# gt-jtx.net
KiCad netlist of a schematic drawn in EAGLE
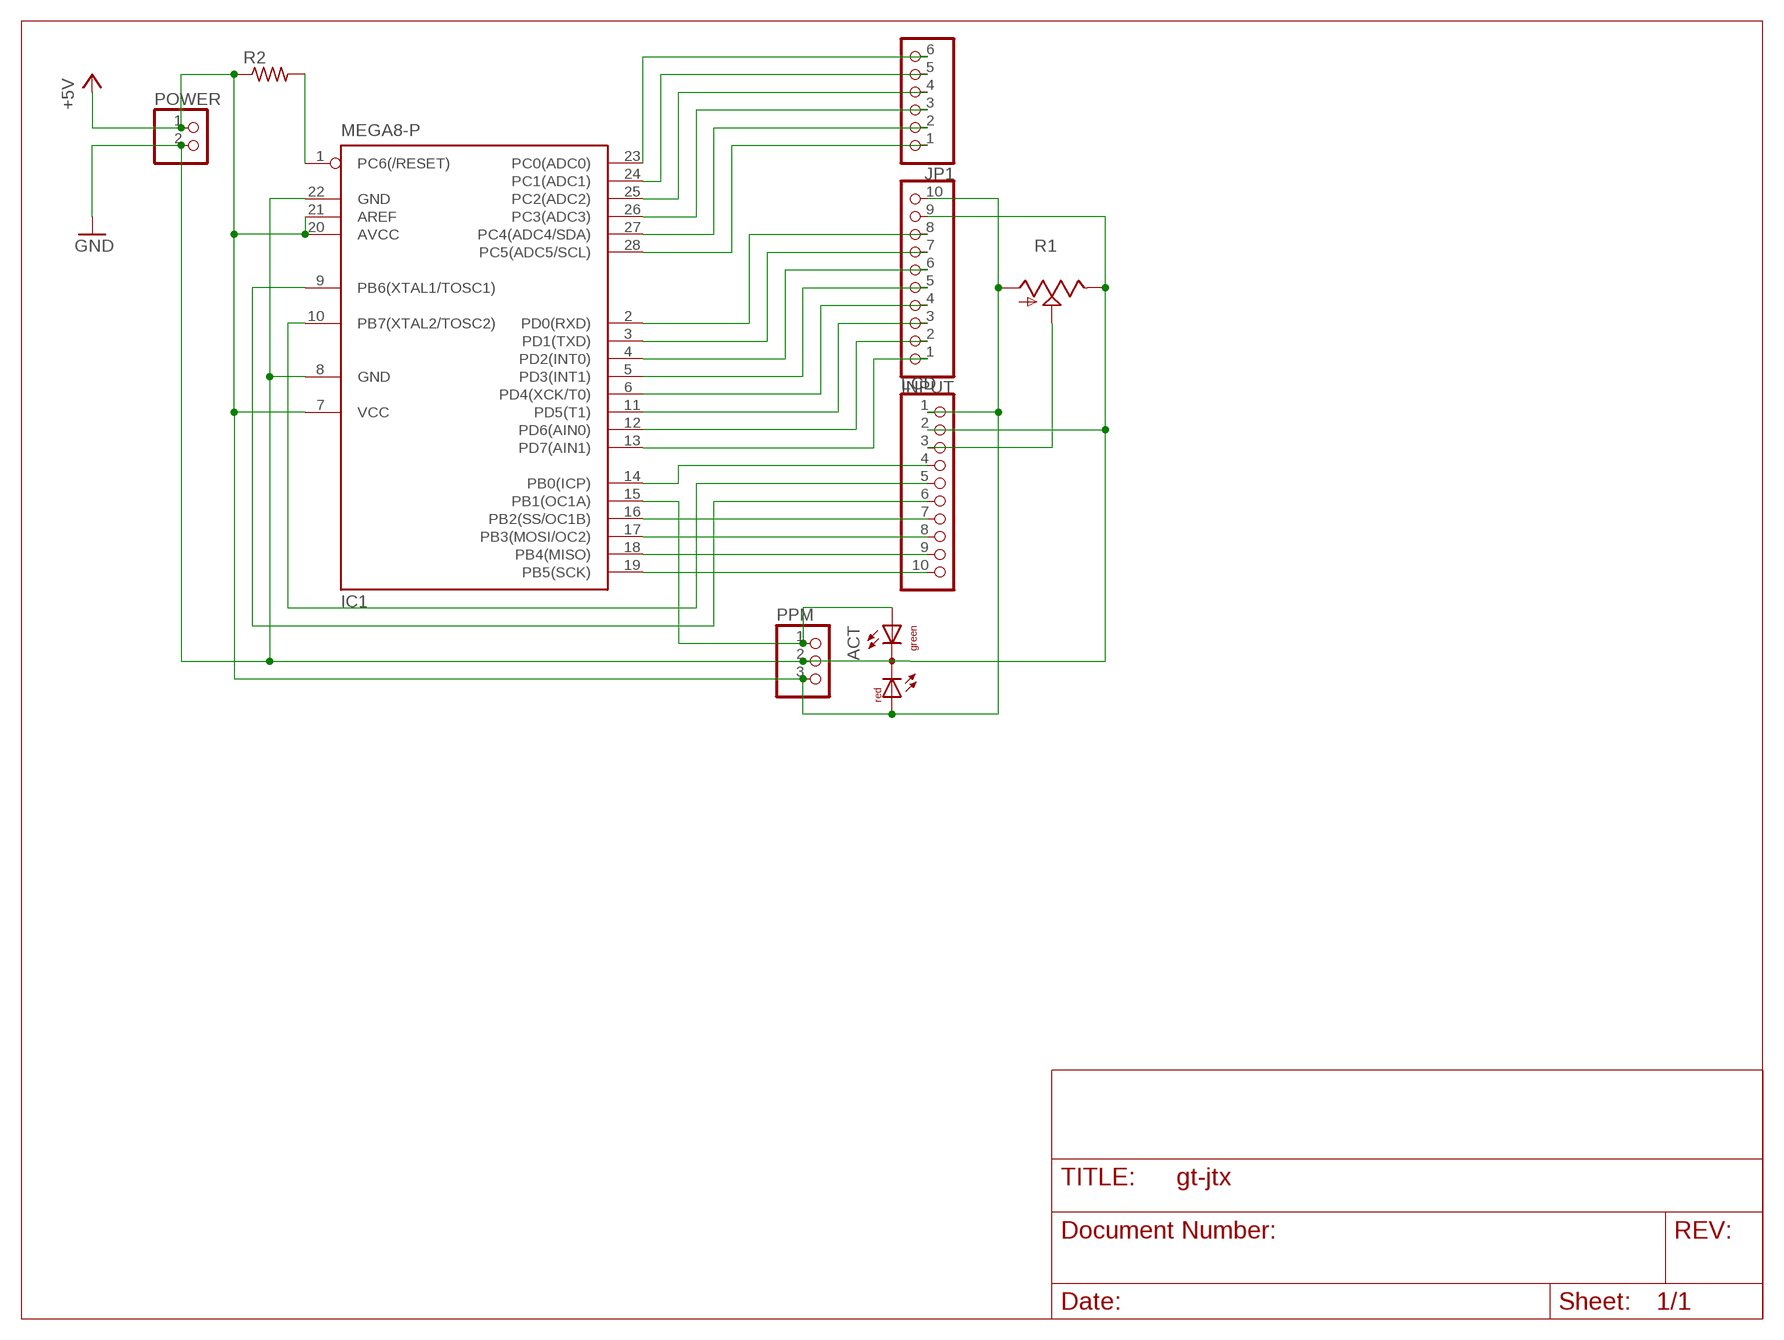
[diagram p0: schematic, sheet 1]

(export (version "E")
  (design (tool "Eeschema 10.0.6"))
  (components
    (comp (ref "ACT")
      (value "DUOLED-RG-C")
      (footprint "eagle-import:DUOLED-C-5MM")
      (libsource (lib "eagle-import") (part "DUOLED-RG-C"))
    )
    (comp (ref "IC1")
      (value "MEGA8-P")
      (footprint "eagle-import:DIL28-3")
      (libsource (lib "eagle-import") (part "MEGA8-P"))
    )
    (comp (ref "INPUT")
      (value "PINHD-1X10")
      (footprint "eagle-import:1X10")
      (libsource (lib "eagle-import") (part "PINHD-1X10"))
    )
    (comp (ref "JP1")
      (value "PINHD-1X6")
      (footprint "eagle-import:1X06")
      (libsource (lib "eagle-import") (part "PINHD-1X6"))
    )
    (comp (ref "LCD")
      (value "PINHD-1X10")
      (footprint "eagle-import:1X10")
      (libsource (lib "eagle-import") (part "PINHD-1X10"))
    )
    (comp (ref "POWER")
      (value "PINHD-1X2")
      (footprint "eagle-import:1X02")
      (libsource (lib "eagle-import") (part "PINHD-1X2"))
    )
    (comp (ref "PPM")
      (value "PINHD-1X3")
      (footprint "eagle-import:1X03")
      (libsource (lib "eagle-import") (part "PINHD-1X3"))
    )
    (comp (ref "R1")
      (value "TRIM_US-CA6V")
      (footprint "eagle-import:CA6V")
      (libsource (lib "eagle-import") (part "TRIM_US-CA6V"))
    )
    (comp (ref "R2")
      (value "R-US_0204/2V")
      (footprint "eagle-import:0204V")
      (libsource (lib "eagle-import") (part "R-US_0204/2V"))
    )
  )
  (nets
    (net (code "1") (name "+5V") (class "Default")
      (node (ref "ACT") (pin "AR") (pinfunction "AR_AR") (pintype "passive"))
      (node (ref "IC1") (pin "20") (pinfunction "AVCC_20") (pintype "power_in"))
      (node (ref "IC1") (pin "21") (pinfunction "AREF_21") (pintype "passive"))
      (node (ref "IC1") (pin "7") (pinfunction "VCC_7") (pintype "power_in"))
      (node (ref "INPUT") (pin "10") (pinfunction "10_10") (pintype "passive"))
      (node (ref "LCD") (pin "1") (pinfunction "1_1") (pintype "passive"))
      (node (ref "POWER") (pin "1") (pinfunction "1_1") (pintype "passive"))
      (node (ref "PPM") (pin "3") (pinfunction "3_3") (pintype "passive"))
      (node (ref "R1") (pin "A") (pinfunction "A_A") (pintype "passive"))
      (node (ref "R2") (pin "1") (pinfunction "1_1") (pintype "passive"))
    )
    (net (code "2") (name "GND") (class "Default")
      (node (ref "ACT") (pin "C") (pinfunction "C_C") (pintype "passive"))
      (node (ref "IC1") (pin "22") (pinfunction "GND_22") (pintype "power_in"))
      (node (ref "IC1") (pin "8") (pinfunction "GND_8") (pintype "power_in"))
      (node (ref "INPUT") (pin "9") (pinfunction "9_9") (pintype "passive"))
      (node (ref "LCD") (pin "2") (pinfunction "2_2") (pintype "passive"))
      (node (ref "POWER") (pin "2") (pinfunction "2_2") (pintype "passive"))
      (node (ref "PPM") (pin "2") (pinfunction "2_2") (pintype "passive"))
      (node (ref "R1") (pin "E") (pinfunction "E_E") (pintype "passive"))
    )
    (net (code "3") (name "Net-(ACT-AG)") (class "Default")
      (node (ref "ACT") (pin "AX") (pinfunction "AG_AX") (pintype "passive"))
      (node (ref "IC1") (pin "15") (pinfunction "PB1(OC1A)_15") (pintype "bidirectional"))
      (node (ref "PPM") (pin "1") (pinfunction "1_1") (pintype "passive"))
    )
    (net (code "4") (name "Net-(IC1-PB0(ICP))") (class "Default")
      (node (ref "IC1") (pin "14") (pinfunction "PB0(ICP)_14") (pintype "bidirectional"))
      (node (ref "LCD") (pin "4") (pinfunction "4_4") (pintype "passive"))
    )
    (net (code "5") (name "Net-(IC1-PB2(SS{slash}OC1B))") (class "Default")
      (node (ref "IC1") (pin "16") (pinfunction "PB2(SS/OC1B)_16") (pintype "bidirectional"))
      (node (ref "LCD") (pin "7") (pinfunction "7_7") (pintype "passive"))
    )
    (net (code "6") (name "Net-(IC1-PB3(MOSI{slash}OC2))") (class "Default")
      (node (ref "IC1") (pin "17") (pinfunction "PB3(MOSI/OC2)_17") (pintype "bidirectional"))
      (node (ref "LCD") (pin "8") (pinfunction "8_8") (pintype "passive"))
    )
    (net (code "7") (name "Net-(IC1-PB4(MISO))") (class "Default")
      (node (ref "IC1") (pin "18") (pinfunction "PB4(MISO)_18") (pintype "bidirectional"))
      (node (ref "LCD") (pin "9") (pinfunction "9_9") (pintype "passive"))
    )
    (net (code "8") (name "Net-(IC1-PB5(SCK))") (class "Default")
      (node (ref "IC1") (pin "19") (pinfunction "PB5(SCK)_19") (pintype "bidirectional"))
      (node (ref "LCD") (pin "10") (pinfunction "10_10") (pintype "passive"))
    )
    (net (code "9") (name "Net-(IC1-PB6(XTAL1{slash}TOSC1))") (class "Default")
      (node (ref "IC1") (pin "9") (pinfunction "PB6(XTAL1/TOSC1)_9") (pintype "bidirectional"))
      (node (ref "LCD") (pin "6") (pinfunction "6_6") (pintype "passive"))
    )
    (net (code "10") (name "Net-(IC1-PB7(XTAL2{slash}TOSC2))") (class "Default")
      (node (ref "IC1") (pin "10") (pinfunction "PB7(XTAL2/TOSC2)_10") (pintype "bidirectional"))
      (node (ref "LCD") (pin "5") (pinfunction "5_5") (pintype "passive"))
    )
    (net (code "11") (name "Net-(IC1-PC0(ADC0))") (class "Default")
      (node (ref "IC1") (pin "23") (pinfunction "PC0(ADC0)_23") (pintype "bidirectional"))
      (node (ref "JP1") (pin "6") (pinfunction "6_6") (pintype "passive"))
    )
    (net (code "12") (name "Net-(IC1-PC1(ADC1))") (class "Default")
      (node (ref "IC1") (pin "24") (pinfunction "PC1(ADC1)_24") (pintype "bidirectional"))
      (node (ref "JP1") (pin "5") (pinfunction "5_5") (pintype "passive"))
    )
    (net (code "13") (name "Net-(IC1-PC2(ADC2))") (class "Default")
      (node (ref "IC1") (pin "25") (pinfunction "PC2(ADC2)_25") (pintype "bidirectional"))
      (node (ref "JP1") (pin "4") (pinfunction "4_4") (pintype "passive"))
    )
    (net (code "14") (name "Net-(IC1-PC3(ADC3))") (class "Default")
      (node (ref "IC1") (pin "26") (pinfunction "PC3(ADC3)_26") (pintype "bidirectional"))
      (node (ref "JP1") (pin "3") (pinfunction "3_3") (pintype "passive"))
    )
    (net (code "15") (name "Net-(IC1-PC4(ADC4{slash}SDA))") (class "Default")
      (node (ref "IC1") (pin "27") (pinfunction "PC4(ADC4/SDA)_27") (pintype "bidirectional"))
      (node (ref "JP1") (pin "2") (pinfunction "2_2") (pintype "passive"))
    )
    (net (code "16") (name "Net-(IC1-PC5(ADC5{slash}SCL))") (class "Default")
      (node (ref "IC1") (pin "28") (pinfunction "PC5(ADC5/SCL)_28") (pintype "bidirectional"))
      (node (ref "JP1") (pin "1") (pinfunction "1_1") (pintype "passive"))
    )
    (net (code "17") (name "Net-(IC1-PC6({slash}RESET))") (class "Default")
      (node (ref "IC1") (pin "1") (pinfunction "PC6(/RESET)_1") (pintype "bidirectional"))
      (node (ref "R2") (pin "2") (pinfunction "2_2") (pintype "passive"))
    )
    (net (code "18") (name "Net-(IC1-PD0(RXD))") (class "Default")
      (node (ref "IC1") (pin "2") (pinfunction "PD0(RXD)_2") (pintype "bidirectional"))
      (node (ref "INPUT") (pin "8") (pinfunction "8_8") (pintype "passive"))
    )
    (net (code "19") (name "Net-(IC1-PD1(TXD))") (class "Default")
      (node (ref "IC1") (pin "3") (pinfunction "PD1(TXD)_3") (pintype "bidirectional"))
      (node (ref "INPUT") (pin "7") (pinfunction "7_7") (pintype "passive"))
    )
    (net (code "20") (name "Net-(IC1-PD2(INT0))") (class "Default")
      (node (ref "IC1") (pin "4") (pinfunction "PD2(INT0)_4") (pintype "bidirectional"))
      (node (ref "INPUT") (pin "6") (pinfunction "6_6") (pintype "passive"))
    )
    (net (code "21") (name "Net-(IC1-PD3(INT1))") (class "Default")
      (node (ref "IC1") (pin "5") (pinfunction "PD3(INT1)_5") (pintype "bidirectional"))
      (node (ref "INPUT") (pin "5") (pinfunction "5_5") (pintype "passive"))
    )
    (net (code "22") (name "Net-(IC1-PD4(XCK{slash}T0))") (class "Default")
      (node (ref "IC1") (pin "6") (pinfunction "PD4(XCK/T0)_6") (pintype "bidirectional"))
      (node (ref "INPUT") (pin "4") (pinfunction "4_4") (pintype "passive"))
    )
    (net (code "23") (name "Net-(IC1-PD5(T1))") (class "Default")
      (node (ref "IC1") (pin "11") (pinfunction "PD5(T1)_11") (pintype "bidirectional"))
      (node (ref "INPUT") (pin "3") (pinfunction "3_3") (pintype "passive"))
    )
    (net (code "24") (name "Net-(IC1-PD6(AIN0))") (class "Default")
      (node (ref "IC1") (pin "12") (pinfunction "PD6(AIN0)_12") (pintype "bidirectional"))
      (node (ref "INPUT") (pin "2") (pinfunction "2_2") (pintype "passive"))
    )
    (net (code "25") (name "Net-(IC1-PD7(AIN1))") (class "Default")
      (node (ref "IC1") (pin "13") (pinfunction "PD7(AIN1)_13") (pintype "bidirectional"))
      (node (ref "INPUT") (pin "1") (pinfunction "1_1") (pintype "passive"))
    )
    (net (code "26") (name "Net-(LCD-Pad3)") (class "Default")
      (node (ref "LCD") (pin "3") (pinfunction "3_3") (pintype "passive"))
      (node (ref "R1") (pin "S") (pinfunction "S_S") (pintype "passive"))
    )
  )
)
